# schematic.net
KiCad netlist of a schematic drawn in EAGLE
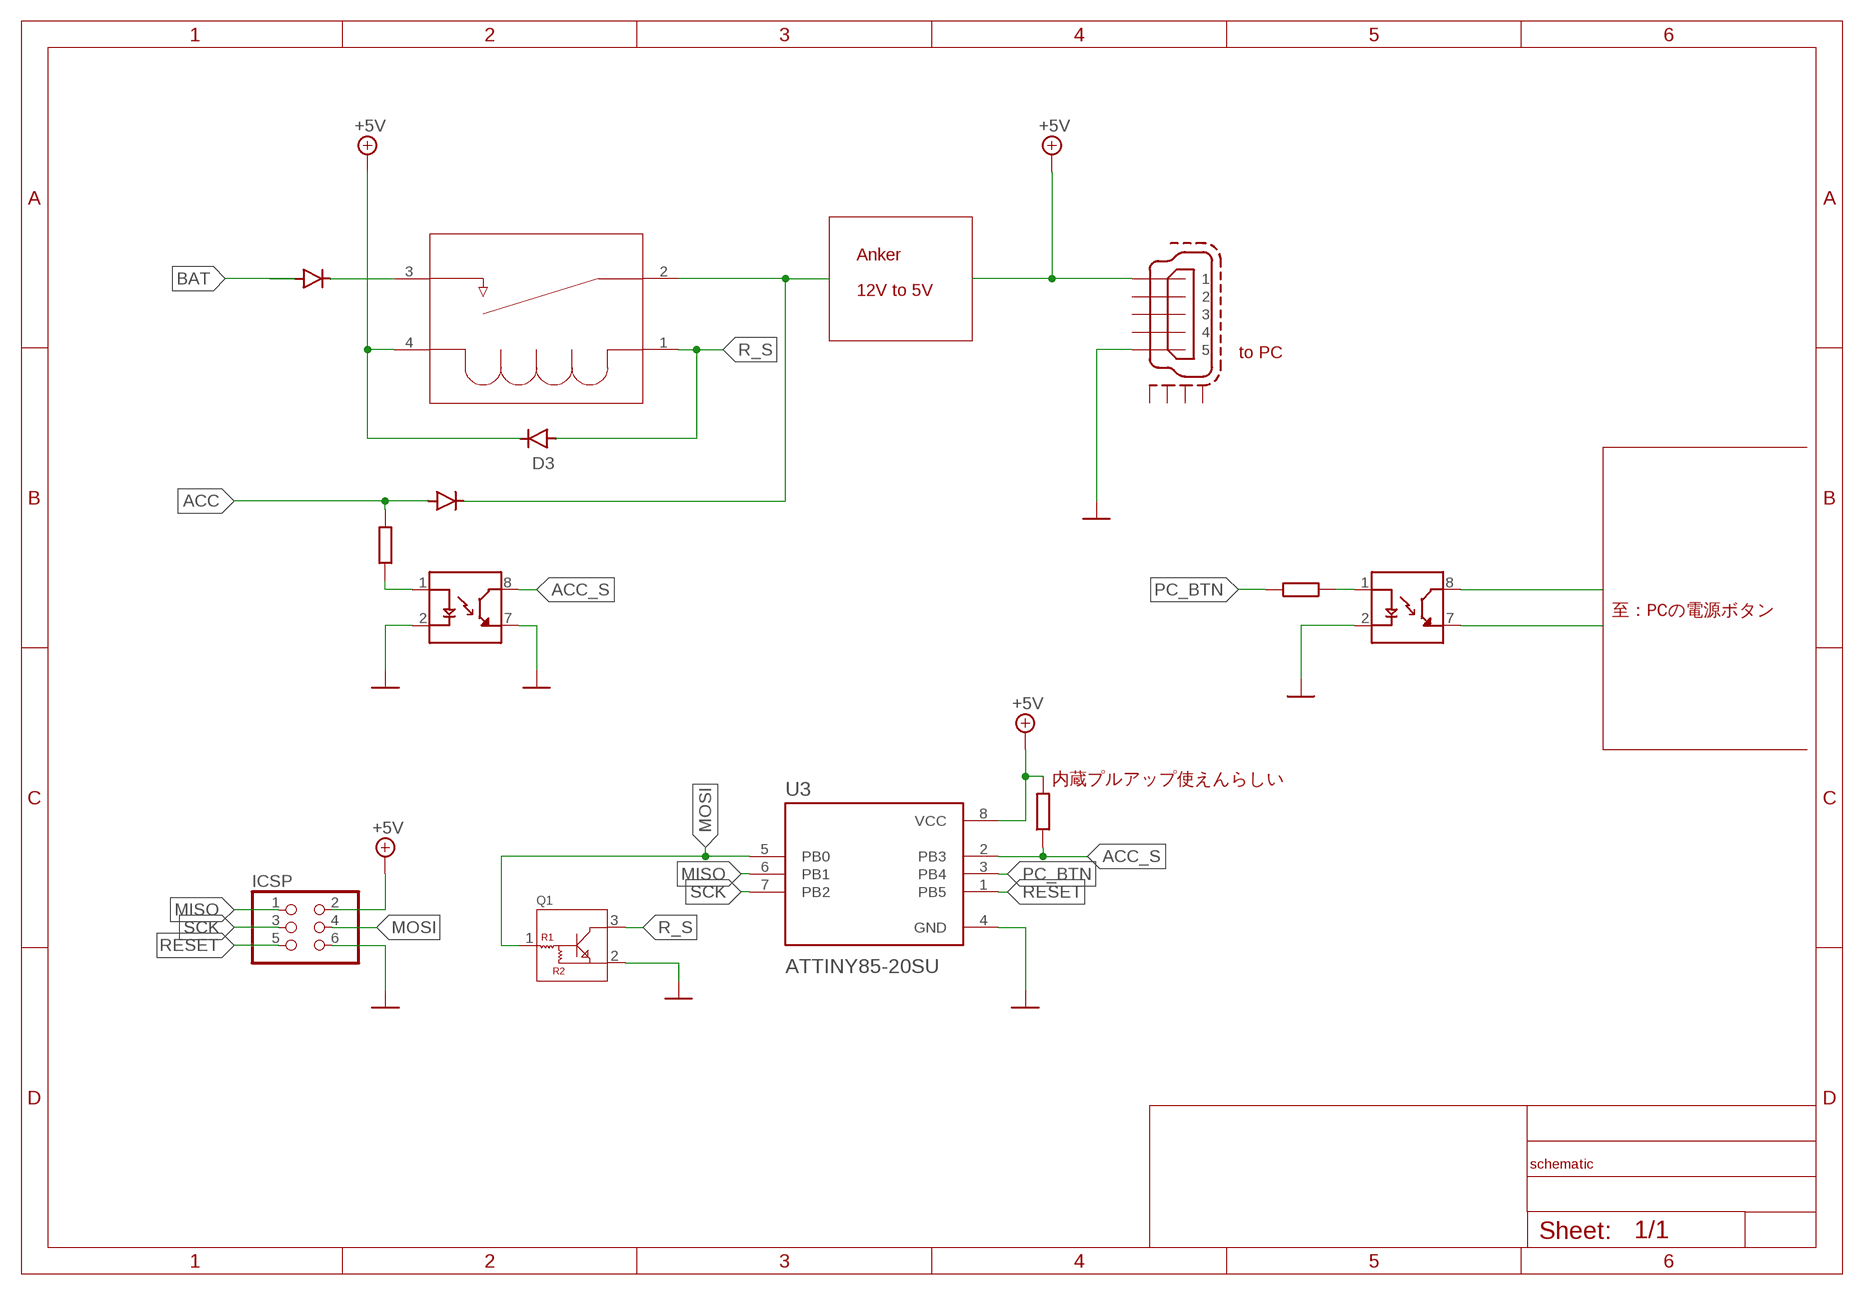
[diagram p0: schematic, sheet 1]

(export (version "E")
  (design (tool "Eeschema 10.0.6"))
  (components
    (comp (ref "D1")
      (value "1N4004")
      (footprint "eagle-import:DO-41")
      (fields
        (field (name "DIGIKEY_PART_NUMBER") "1N4004MSCT-ND")
        (field (name "MANUFACTURER") "Micro Commercial Co")
        (field (name "CREATED_BY") "PCBLayout.com")
      )
      (libsource (lib "eagle-import") (part "1N4004"))
    )
    (comp (ref "D3")
      (value "1N4004")
      (footprint "eagle-import:DO-41")
      (fields
        (field (name "DIGIKEY_PART_NUMBER") "1N4004MSCT-ND")
        (field (name "MANUFACTURER") "Micro Commercial Co")
        (field (name "CREATED_BY") "PCBLayout.com")
      )
      (libsource (lib "eagle-import") (part "1N4004"))
    )
    (comp (ref "D4")
      (value "1N4004")
      (footprint "eagle-import:DO-41")
      (fields
        (field (name "DIGIKEY_PART_NUMBER") "1N4004MSCT-ND")
        (field (name "MANUFACTURER") "Micro Commercial Co")
        (field (name "CREATED_BY") "PCBLayout.com")
      )
      (libsource (lib "eagle-import") (part "1N4004"))
    )
    (comp (ref "ICSP")
      (value "PINHD-2X3")
      (footprint "eagle-import:2X03")
      (libsource (lib "eagle-import") (part "PINHD-2X3"))
    )
    (comp (ref "Q1")
      (value "DTC114EM3T5G")
      (footprint "eagle-import:VMT3")
      (fields (field (name "MF") "Nexperia USA") (field (name "MP") "DTC114E"))
      (libsource (lib "eagle-import") (part "DTC114EM3T5G"))
    )
    (comp (ref "R1")
      (value "R-EU_0204/5")
      (footprint "eagle-import:0204_5")
      (libsource (lib "eagle-import") (part "R-EU_0204/5"))
    )
    (comp (ref "R2")
      (value "R-EU_0204/5")
      (footprint "eagle-import:0204_5")
      (libsource (lib "eagle-import") (part "R-EU_0204/5"))
    )
    (comp (ref "R3")
      (value "R-EU_0204/5")
      (footprint "eagle-import:0204_5")
      (libsource (lib "eagle-import") (part "R-EU_0204/5"))
    )
    (comp (ref "U1")
      (value "2-1393222-0")
      (footprint "eagle-import:RELAY6-4-394X1126_591")
      (fields (field (name "COPYRIGHT") "Copyright (C) 2016 Accelerated Designs. All rights reserved"))
      (libsource (lib "eagle-import") (part "2-1393222-0"))
    )
    (comp (ref "U2")
      (value "TLP627-2")
      (footprint "eagle-import:DIP762W50P254L966H455Q8")
      (fields (field (name "MF") "Toshiba"))
      (libsource (lib "eagle-import") (part "TLP627-2"))
    )
    (comp (ref "U3")
      (value "ATTINY85-20SU")
      (footprint "eagle-import:SOIC127P798X216-8N")
      (fields (field (name "MF") "Microchip Technology / Atmel"))
      (libsource (lib "eagle-import") (part "ATTINY85-20SU"))
    )
    (comp (ref "U4")
      (value "TLP627-2")
      (footprint "eagle-import:DIP762W50P254L966H455Q8")
      (fields (field (name "MF") "Toshiba"))
      (libsource (lib "eagle-import") (part "TLP627-2"))
    )
    (comp (ref "X1")
      (value "C-05843_USB-MINI-B32005-201")
      (footprint "eagle-import:32005-201")
      (libsource (lib "eagle-import") (part "C-05843_USB-MINI-B32005-201"))
    )
  )
  (nets
    (net (code "1") (name "+5V") (class "Default")
      (node (ref "D3") (pin "C") (pinfunction "C_C") (pintype "passive"))
      (node (ref "ICSP") (pin "2") (pinfunction "2_2") (pintype "passive"))
      (node (ref "R2") (pin "2") (pinfunction "2_2") (pintype "passive"))
      (node (ref "U1") (pin "4") (pinfunction "4_4") (pintype "passive"))
      (node (ref "U3") (pin "8") (pinfunction "VCC_8") (pintype "power_in"))
      (node (ref "X1") (pin "1") (pinfunction "1_1") (pintype "passive"))
    )
    (net (code "2") (name "ACC") (class "Default")
      (node (ref "D4") (pin "A") (pinfunction "A_A") (pintype "passive"))
      (node (ref "D4") (pin "C") (pinfunction "C_C") (pintype "passive"))
      (node (ref "R1") (pin "2") (pinfunction "2_2") (pintype "passive"))
      (node (ref "U1") (pin "2") (pinfunction "2_2") (pintype "passive"))
    )
    (net (code "3") (name "ACC_S") (class "Default")
      (node (ref "R2") (pin "1") (pinfunction "1_1") (pintype "passive"))
      (node (ref "U2") (pin "8") (pinfunction "CT1_8") (pintype "passive"))
      (node (ref "U3") (pin "2") (pinfunction "PB3_2") (pintype "bidirectional"))
    )
    (net (code "4") (name "BAT") (class "Default")
      (node (ref "D1") (pin "A") (pinfunction "A_A") (pintype "passive"))
    )
    (net (code "5") (name "GND") (class "Default")
      (node (ref "ICSP") (pin "6") (pinfunction "6_6") (pintype "passive"))
      (node (ref "Q1") (pin "2") (pinfunction "2_2") (pintype "passive"))
      (node (ref "U2") (pin "2") (pinfunction "C1_2") (pintype "passive"))
      (node (ref "U2") (pin "7") (pinfunction "ET1_7") (pintype "passive"))
      (node (ref "U3") (pin "4") (pinfunction "GND_4") (pintype "power_in"))
      (node (ref "U4") (pin "2") (pinfunction "C1_2") (pintype "passive"))
      (node (ref "X1") (pin "5") (pinfunction "5_5") (pintype "passive"))
    )
    (net (code "6") (name "MISO") (class "Default")
      (node (ref "ICSP") (pin "1") (pinfunction "1_1") (pintype "passive"))
      (node (ref "U3") (pin "6") (pinfunction "PB1_6") (pintype "bidirectional"))
    )
    (net (code "7") (name "MOSI") (class "Default")
      (node (ref "ICSP") (pin "4") (pinfunction "4_4") (pintype "passive"))
      (node (ref "Q1") (pin "1") (pinfunction "1_1") (pintype "passive"))
      (node (ref "U3") (pin "5") (pinfunction "PB0_5") (pintype "bidirectional"))
    )
    (net (code "8") (name "Net-(D1-PadC)") (class "Default")
      (node (ref "D1") (pin "C") (pinfunction "C_C") (pintype "passive"))
      (node (ref "U1") (pin "3") (pinfunction "3_3") (pintype "passive"))
    )
    (net (code "9") (name "Net-(U2A-A1)") (class "Default")
      (node (ref "R1") (pin "1") (pinfunction "1_1") (pintype "passive"))
      (node (ref "U2") (pin "1") (pinfunction "A1_1") (pintype "passive"))
    )
    (net (code "10") (name "Net-(U4A-A1)") (class "Default")
      (node (ref "R3") (pin "1") (pinfunction "1_1") (pintype "passive"))
      (node (ref "U4") (pin "1") (pinfunction "A1_1") (pintype "passive"))
    )
    (net (code "11") (name "PC_BTN") (class "Default")
      (node (ref "R3") (pin "2") (pinfunction "2_2") (pintype "passive"))
      (node (ref "U3") (pin "3") (pinfunction "PB4_3") (pintype "bidirectional"))
    )
    (net (code "12") (name "RESET") (class "Default")
      (node (ref "ICSP") (pin "5") (pinfunction "5_5") (pintype "passive"))
      (node (ref "U3") (pin "1") (pinfunction "PB5_1") (pintype "bidirectional"))
    )
    (net (code "13") (name "R_S") (class "Default")
      (node (ref "D3") (pin "A") (pinfunction "A_A") (pintype "passive"))
      (node (ref "Q1") (pin "3") (pinfunction "3_3") (pintype "passive"))
      (node (ref "U1") (pin "1") (pinfunction "1_1") (pintype "passive"))
    )
    (net (code "14") (name "SCK") (class "Default")
      (node (ref "ICSP") (pin "3") (pinfunction "3_3") (pintype "passive"))
      (node (ref "U3") (pin "7") (pinfunction "PB2_7") (pintype "bidirectional"))
    )
    (net (code "15") (name "unconnected-(U4A-CT1-Pad8)") (class "Default")
      (node (ref "U4") (pin "8") (pinfunction "CT1_8") (pintype "passive"))
    )
    (net (code "16") (name "unconnected-(U4A-ET1-Pad7)") (class "Default")
      (node (ref "U4") (pin "7") (pinfunction "ET1_7") (pintype "passive"))
    )
    (net (code "17") (name "unconnected-(X1-Pad2)") (class "Default")
      (node (ref "X1") (pin "2") (pinfunction "2_2") (pintype "passive"))
    )
    (net (code "18") (name "unconnected-(X1-Pad3)") (class "Default")
      (node (ref "X1") (pin "3") (pinfunction "3_3") (pintype "passive"))
    )
    (net (code "19") (name "unconnected-(X1-Pad4)") (class "Default")
      (node (ref "X1") (pin "4") (pinfunction "4_4") (pintype "passive"))
    )
    (net (code "20") (name "unconnected-(X1B-S1-PadM1)") (class "Default")
      (node (ref "X1") (pin "M1") (pinfunction "S1_M1") (pintype "passive"))
    )
    (net (code "21") (name "unconnected-(X1B-S2-PadM2)") (class "Default")
      (node (ref "X1") (pin "M2") (pinfunction "S2_M2") (pintype "passive"))
    )
    (net (code "22") (name "unconnected-(X1B-S3-PadM3)") (class "Default")
      (node (ref "X1") (pin "M3") (pinfunction "S3_M3") (pintype "passive"))
    )
    (net (code "23") (name "unconnected-(X1B-S4-PadM4)") (class "Default")
      (node (ref "X1") (pin "M4") (pinfunction "S4_M4") (pintype "passive"))
    )
  )
)
